# MacroMicro_v27.net
KiCad netlist of a schematic drawn in EAGLE
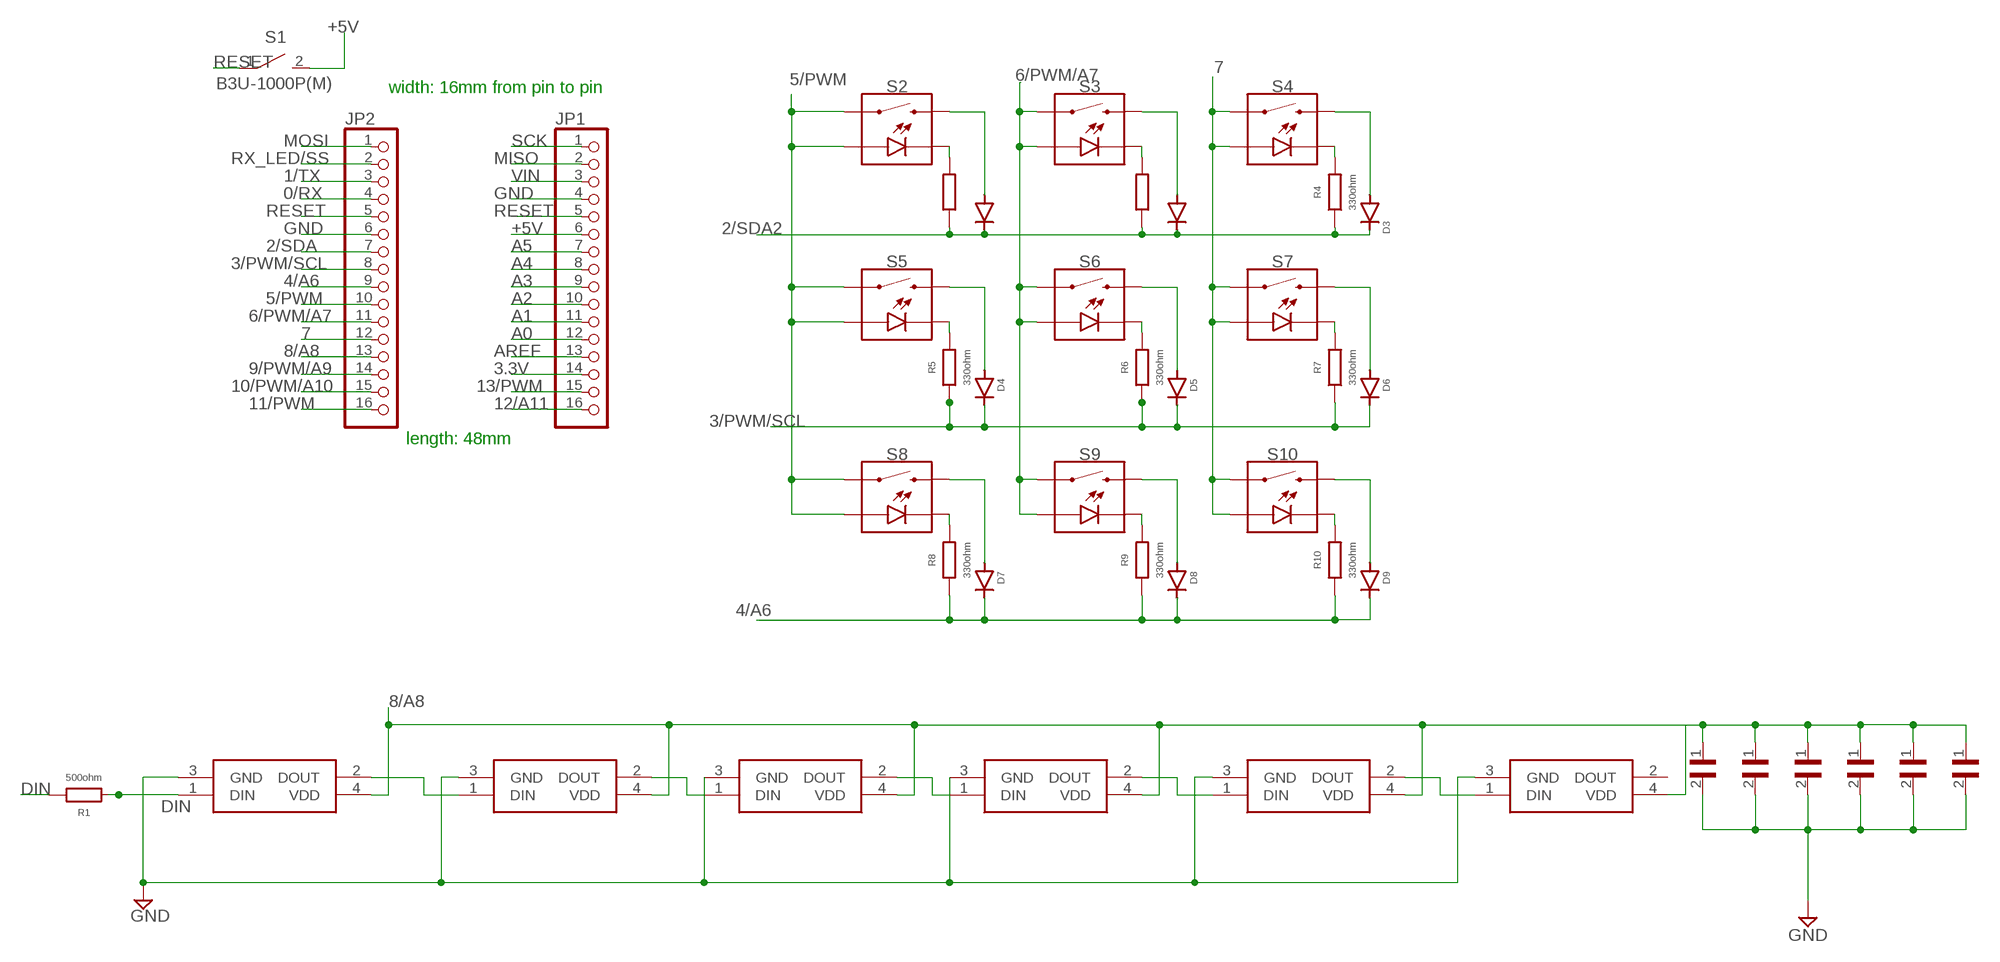
[diagram p0: schematic, sheet 1]

(export (version "E")
  (design (tool "Eeschema 10.0.6"))
  (components
    (comp (ref "C1")
      (value "0.1uf")
      (footprint "eagle-import:CAPC1608X80N")
      (fields
        (field (name "DIGI-KEY_PART_NUMBER") "1608-1306-1-ND")
        (field (name "MF") "Knowles Syfer")
        (field (name "MP") "0603Y0500104KET")
      )
      (libsource (lib "eagle-import") (part "0603Y0500104KET"))
    )
    (comp (ref "C2")
      (value "0.1uf")
      (footprint "eagle-import:CAPC1608X80N")
      (fields
        (field (name "DIGI-KEY_PART_NUMBER") "1608-1306-1-ND")
        (field (name "MF") "Knowles Syfer")
        (field (name "MP") "0603Y0500104KET")
      )
      (libsource (lib "eagle-import") (part "0603Y0500104KET"))
    )
    (comp (ref "C3")
      (value "0.1uf")
      (footprint "eagle-import:CAPC1608X80N")
      (fields
        (field (name "DIGI-KEY_PART_NUMBER") "1608-1306-1-ND")
        (field (name "MF") "Knowles Syfer")
        (field (name "MP") "0603Y0500104KET")
      )
      (libsource (lib "eagle-import") (part "0603Y0500104KET"))
    )
    (comp (ref "C4")
      (value "0.1uf")
      (footprint "eagle-import:CAPC1608X80N")
      (fields
        (field (name "DIGI-KEY_PART_NUMBER") "1608-1306-1-ND")
        (field (name "MF") "Knowles Syfer")
        (field (name "MP") "0603Y0500104KET")
      )
      (libsource (lib "eagle-import") (part "0603Y0500104KET"))
    )
    (comp (ref "C5")
      (value "0.1uf")
      (footprint "eagle-import:CAPC1608X80N")
      (fields
        (field (name "DIGI-KEY_PART_NUMBER") "1608-1306-1-ND")
        (field (name "MF") "Knowles Syfer")
        (field (name "MP") "0603Y0500104KET")
      )
      (libsource (lib "eagle-import") (part "0603Y0500104KET"))
    )
    (comp (ref "C6")
      (value "0.1uf")
      (footprint "eagle-import:CAPC1608X80N")
      (fields
        (field (name "DIGI-KEY_PART_NUMBER") "1608-1306-1-ND")
        (field (name "MF") "Knowles Syfer")
        (field (name "MP") "0603Y0500104KET")
      )
      (libsource (lib "eagle-import") (part "0603Y0500104KET"))
    )
    (comp (ref "D1")
      (value "1N4148WS")
      (footprint "eagle-import:SOD-323")
      (fields
        (field (name "DIGIKEY_PART_NUMBER") "1N4148WSFSTR-ND")
        (field (name "MANUFACTURER") "Diodes Incorporated")
        (field (name "CREATED_BY") "PCBLayout.com")
      )
      (libsource (lib "eagle-import") (part "1N4148WS"))
    )
    (comp (ref "D2")
      (value "1N4148WS")
      (footprint "eagle-import:SOD-323")
      (fields
        (field (name "DIGIKEY_PART_NUMBER") "1N4148WSFSTR-ND")
        (field (name "MANUFACTURER") "Diodes Incorporated")
        (field (name "CREATED_BY") "PCBLayout.com")
      )
      (libsource (lib "eagle-import") (part "1N4148WS"))
    )
    (comp (ref "D3")
      (value "1N4148WS")
      (footprint "eagle-import:SOD-323")
      (fields
        (field (name "DIGIKEY_PART_NUMBER") "1N4148WSFSTR-ND")
        (field (name "MANUFACTURER") "Diodes Incorporated")
        (field (name "CREATED_BY") "PCBLayout.com")
      )
      (libsource (lib "eagle-import") (part "1N4148WS"))
    )
    (comp (ref "D4")
      (value "1N4148WS")
      (footprint "eagle-import:SOD-323")
      (fields
        (field (name "DIGIKEY_PART_NUMBER") "1N4148WSFSTR-ND")
        (field (name "MANUFACTURER") "Diodes Incorporated")
        (field (name "CREATED_BY") "PCBLayout.com")
      )
      (libsource (lib "eagle-import") (part "1N4148WS"))
    )
    (comp (ref "D5")
      (value "1N4148WS")
      (footprint "eagle-import:SOD-323")
      (fields
        (field (name "DIGIKEY_PART_NUMBER") "1N4148WSFSTR-ND")
        (field (name "MANUFACTURER") "Diodes Incorporated")
        (field (name "CREATED_BY") "PCBLayout.com")
      )
      (libsource (lib "eagle-import") (part "1N4148WS"))
    )
    (comp (ref "D6")
      (value "1N4148WS")
      (footprint "eagle-import:SOD-323")
      (fields
        (field (name "DIGIKEY_PART_NUMBER") "1N4148WSFSTR-ND")
        (field (name "MANUFACTURER") "Diodes Incorporated")
        (field (name "CREATED_BY") "PCBLayout.com")
      )
      (libsource (lib "eagle-import") (part "1N4148WS"))
    )
    (comp (ref "D7")
      (value "1N4148WS")
      (footprint "eagle-import:SOD-323")
      (fields
        (field (name "DIGIKEY_PART_NUMBER") "1N4148WSFSTR-ND")
        (field (name "MANUFACTURER") "Diodes Incorporated")
        (field (name "CREATED_BY") "PCBLayout.com")
      )
      (libsource (lib "eagle-import") (part "1N4148WS"))
    )
    (comp (ref "D8")
      (value "1N4148WS")
      (footprint "eagle-import:SOD-323")
      (fields
        (field (name "DIGIKEY_PART_NUMBER") "1N4148WSFSTR-ND")
        (field (name "MANUFACTURER") "Diodes Incorporated")
        (field (name "CREATED_BY") "PCBLayout.com")
      )
      (libsource (lib "eagle-import") (part "1N4148WS"))
    )
    (comp (ref "D9")
      (value "1N4148WS")
      (footprint "eagle-import:SOD-323")
      (fields
        (field (name "DIGIKEY_PART_NUMBER") "1N4148WSFSTR-ND")
        (field (name "MANUFACTURER") "Diodes Incorporated")
        (field (name "CREATED_BY") "PCBLayout.com")
      )
      (libsource (lib "eagle-import") (part "1N4148WS"))
    )
    (comp (ref "JP1")
      (value "PINHD-1X16")
      (footprint "eagle-import:1X16")
      (libsource (lib "eagle-import") (part "PINHD-1X16"))
    )
    (comp (ref "JP2")
      (value "PINHD-1X16")
      (footprint "eagle-import:1X16")
      (libsource (lib "eagle-import") (part "PINHD-1X16"))
    )
    (comp (ref "LED1")
      (value "SK6812MINI-E")
      (footprint "eagle-import:SK6812MINIE")
      (libsource (lib "eagle-import") (part "SK6812MINI-E"))
    )
    (comp (ref "LED2")
      (value "SK6812MINI-E")
      (footprint "eagle-import:SK6812MINIE")
      (libsource (lib "eagle-import") (part "SK6812MINI-E"))
    )
    (comp (ref "LED3")
      (value "SK6812MINI-E")
      (footprint "eagle-import:SK6812MINIE")
      (libsource (lib "eagle-import") (part "SK6812MINI-E"))
    )
    (comp (ref "LED4")
      (value "SK6812MINI-E")
      (footprint "eagle-import:SK6812MINIE")
      (libsource (lib "eagle-import") (part "SK6812MINI-E"))
    )
    (comp (ref "LED5")
      (value "SK6812MINI-E")
      (footprint "eagle-import:SK6812MINIE")
      (libsource (lib "eagle-import") (part "SK6812MINI-E"))
    )
    (comp (ref "LED6")
      (value "SK6812MINI-E")
      (footprint "eagle-import:SK6812MINIE")
      (libsource (lib "eagle-import") (part "SK6812MINI-E"))
    )
    (comp (ref "R1")
      (value "500ohm")
      (footprint "eagle-import:RESC3216X70")
      (libsource (lib "eagle-import") (part "RCHIP-1206(3216-METRIC)_"))
    )
    (comp (ref "R2")
      (value "330ohm")
      (footprint "eagle-import:RESC3216X70")
      (libsource (lib "eagle-import") (part "RCHIP-1206(3216-METRIC)_"))
    )
    (comp (ref "R3")
      (value "330ohm")
      (footprint "eagle-import:RESC3216X70")
      (libsource (lib "eagle-import") (part "RCHIP-1206(3216-METRIC)_"))
    )
    (comp (ref "R4")
      (value "330ohm")
      (footprint "eagle-import:RESC3216X70")
      (libsource (lib "eagle-import") (part "RCHIP-1206(3216-METRIC)_"))
    )
    (comp (ref "R5")
      (value "330ohm")
      (footprint "eagle-import:RESC3216X70")
      (libsource (lib "eagle-import") (part "RCHIP-1206(3216-METRIC)_"))
    )
    (comp (ref "R6")
      (value "330ohm")
      (footprint "eagle-import:RESC3216X70")
      (libsource (lib "eagle-import") (part "RCHIP-1206(3216-METRIC)_"))
    )
    (comp (ref "R7")
      (value "330ohm")
      (footprint "eagle-import:RESC3216X70")
      (libsource (lib "eagle-import") (part "RCHIP-1206(3216-METRIC)_"))
    )
    (comp (ref "R8")
      (value "330ohm")
      (footprint "eagle-import:RESC3216X70")
      (libsource (lib "eagle-import") (part "RCHIP-1206(3216-METRIC)_"))
    )
    (comp (ref "R9")
      (value "330ohm")
      (footprint "eagle-import:RESC3216X70")
      (libsource (lib "eagle-import") (part "RCHIP-1206(3216-METRIC)_"))
    )
    (comp (ref "R10")
      (value "330ohm")
      (footprint "eagle-import:RESC3216X70")
      (libsource (lib "eagle-import") (part "RCHIP-1206(3216-METRIC)_"))
    )
    (comp (ref "S1")
      (value "B3U-1000P(M)")
      (footprint "eagle-import:B3U-1000P(M)")
      (fields (field (name "MANUFACTURER") "OMRON"))
      (libsource (lib "eagle-import") (part "B3U-X0001000P(M)B3U-1000P(M)"))
    )
    (comp (ref "S2")
      (value "MOMENTARY-SWITCH-SPST-LED-PTH-CHERRY")
      (footprint "eagle-import:CHERRY-MX-LED")
      (libsource (lib "eagle-import") (part "MOMENTARY-SWITCH-SPST-LED-PTH-CHERRY"))
    )
    (comp (ref "S3")
      (value "MOMENTARY-SWITCH-SPST-LED-PTH-CHERRY")
      (footprint "eagle-import:CHERRY-MX-LED")
      (libsource (lib "eagle-import") (part "MOMENTARY-SWITCH-SPST-LED-PTH-CHERRY"))
    )
    (comp (ref "S4")
      (value "MOMENTARY-SWITCH-SPST-LED-PTH-CHERRY")
      (footprint "eagle-import:CHERRY-MX-LED")
      (libsource (lib "eagle-import") (part "MOMENTARY-SWITCH-SPST-LED-PTH-CHERRY"))
    )
    (comp (ref "S5")
      (value "MOMENTARY-SWITCH-SPST-LED-PTH-CHERRY")
      (footprint "eagle-import:CHERRY-MX-LED")
      (libsource (lib "eagle-import") (part "MOMENTARY-SWITCH-SPST-LED-PTH-CHERRY"))
    )
    (comp (ref "S6")
      (value "MOMENTARY-SWITCH-SPST-LED-PTH-CHERRY")
      (footprint "eagle-import:CHERRY-MX-LED")
      (libsource (lib "eagle-import") (part "MOMENTARY-SWITCH-SPST-LED-PTH-CHERRY"))
    )
    (comp (ref "S7")
      (value "MOMENTARY-SWITCH-SPST-LED-PTH-CHERRY")
      (footprint "eagle-import:CHERRY-MX-LED")
      (libsource (lib "eagle-import") (part "MOMENTARY-SWITCH-SPST-LED-PTH-CHERRY"))
    )
    (comp (ref "S8")
      (value "MOMENTARY-SWITCH-SPST-LED-PTH-CHERRY")
      (footprint "eagle-import:CHERRY-MX-LED")
      (libsource (lib "eagle-import") (part "MOMENTARY-SWITCH-SPST-LED-PTH-CHERRY"))
    )
    (comp (ref "S9")
      (value "MOMENTARY-SWITCH-SPST-LED-PTH-CHERRY")
      (footprint "eagle-import:CHERRY-MX-LED")
      (libsource (lib "eagle-import") (part "MOMENTARY-SWITCH-SPST-LED-PTH-CHERRY"))
    )
    (comp (ref "S10")
      (value "MOMENTARY-SWITCH-SPST-LED-PTH-CHERRY")
      (footprint "eagle-import:CHERRY-MX-LED")
      (libsource (lib "eagle-import") (part "MOMENTARY-SWITCH-SPST-LED-PTH-CHERRY"))
    )
  )
  (nets
    (net (code "1") (name "/+5V") (class "Default")
      (node (ref "JP1") (pin "6") (pinfunction "6_6") (pintype "passive"))
      (node (ref "S1") (pin "2") (pinfunction "2_2") (pintype "bidirectional"))
    )
    (net (code "2") (name "/0{slash}RX") (class "Default")
      (node (ref "JP2") (pin "4") (pinfunction "4_4") (pintype "passive"))
    )
    (net (code "3") (name "/1{slash}TX") (class "Default")
      (node (ref "JP2") (pin "3") (pinfunction "3_3") (pintype "passive"))
    )
    (net (code "4") (name "/2{slash}SDA") (class "Default")
      (node (ref "JP2") (pin "7") (pinfunction "7_7") (pintype "passive"))
    )
    (net (code "5") (name "/2{slash}SDA2") (class "Default")
      (node (ref "D1") (pin "C") (pinfunction "C_C") (pintype "passive"))
      (node (ref "D2") (pin "C") (pinfunction "C_C") (pintype "passive"))
      (node (ref "D3") (pin "C") (pinfunction "C_C") (pintype "passive"))
      (node (ref "R2") (pin "1") (pinfunction "1_1") (pintype "passive"))
      (node (ref "R3") (pin "1") (pinfunction "1_1") (pintype "passive"))
      (node (ref "R4") (pin "1") (pinfunction "1_1") (pintype "passive"))
    )
    (net (code "6") (name "/3.3V") (class "Default")
      (node (ref "JP1") (pin "14") (pinfunction "14_14") (pintype "passive"))
    )
    (net (code "7") (name "/3{slash}PWM{slash}SCL") (class "Default")
      (node (ref "D4") (pin "C") (pinfunction "C_C") (pintype "passive"))
      (node (ref "D5") (pin "C") (pinfunction "C_C") (pintype "passive"))
      (node (ref "D6") (pin "C") (pinfunction "C_C") (pintype "passive"))
      (node (ref "JP2") (pin "8") (pinfunction "8_8") (pintype "passive"))
      (node (ref "R5") (pin "1") (pinfunction "1_1") (pintype "passive"))
      (node (ref "R6") (pin "1") (pinfunction "1_1") (pintype "passive"))
      (node (ref "R7") (pin "1") (pinfunction "1_1") (pintype "passive"))
    )
    (net (code "8") (name "/4{slash}A6") (class "Default")
      (node (ref "D7") (pin "C") (pinfunction "C_C") (pintype "passive"))
      (node (ref "D8") (pin "C") (pinfunction "C_C") (pintype "passive"))
      (node (ref "D9") (pin "C") (pinfunction "C_C") (pintype "passive"))
      (node (ref "JP2") (pin "9") (pinfunction "9_9") (pintype "passive"))
      (node (ref "R10") (pin "1") (pinfunction "1_1") (pintype "passive"))
      (node (ref "R8") (pin "1") (pinfunction "1_1") (pintype "passive"))
      (node (ref "R9") (pin "1") (pinfunction "1_1") (pintype "passive"))
    )
    (net (code "9") (name "/5{slash}PWM") (class "Default")
      (node (ref "JP2") (pin "10") (pinfunction "10_10") (pintype "passive"))
      (node (ref "S2") (pin "A") (pinfunction "A_A") (pintype "passive"))
      (node (ref "S2") (pin "S1") (pinfunction "1_S1") (pintype "passive"))
      (node (ref "S5") (pin "A") (pinfunction "A_A") (pintype "passive"))
      (node (ref "S5") (pin "S1") (pinfunction "1_S1") (pintype "passive"))
      (node (ref "S8") (pin "A") (pinfunction "A_A") (pintype "passive"))
      (node (ref "S8") (pin "S1") (pinfunction "1_S1") (pintype "passive"))
    )
    (net (code "10") (name "/6{slash}PWM{slash}A7") (class "Default")
      (node (ref "JP2") (pin "11") (pinfunction "11_11") (pintype "passive"))
      (node (ref "S3") (pin "A") (pinfunction "A_A") (pintype "passive"))
      (node (ref "S3") (pin "S1") (pinfunction "1_S1") (pintype "passive"))
      (node (ref "S6") (pin "A") (pinfunction "A_A") (pintype "passive"))
      (node (ref "S6") (pin "S1") (pinfunction "1_S1") (pintype "passive"))
      (node (ref "S9") (pin "A") (pinfunction "A_A") (pintype "passive"))
      (node (ref "S9") (pin "S1") (pinfunction "1_S1") (pintype "passive"))
    )
    (net (code "11") (name "/7") (class "Default")
      (node (ref "JP2") (pin "12") (pinfunction "12_12") (pintype "passive"))
      (node (ref "S10") (pin "A") (pinfunction "A_A") (pintype "passive"))
      (node (ref "S10") (pin "S1") (pinfunction "1_S1") (pintype "passive"))
      (node (ref "S4") (pin "A") (pinfunction "A_A") (pintype "passive"))
      (node (ref "S4") (pin "S1") (pinfunction "1_S1") (pintype "passive"))
      (node (ref "S7") (pin "A") (pinfunction "A_A") (pintype "passive"))
      (node (ref "S7") (pin "S1") (pinfunction "1_S1") (pintype "passive"))
    )
    (net (code "12") (name "/8{slash}A8") (class "Default")
      (node (ref "C1") (pin "1") (pinfunction "1_1") (pintype "passive"))
      (node (ref "C2") (pin "1") (pinfunction "1_1") (pintype "passive"))
      (node (ref "C3") (pin "1") (pinfunction "1_1") (pintype "passive"))
      (node (ref "C4") (pin "1") (pinfunction "1_1") (pintype "passive"))
      (node (ref "C5") (pin "1") (pinfunction "1_1") (pintype "passive"))
      (node (ref "C6") (pin "1") (pinfunction "1_1") (pintype "passive"))
      (node (ref "JP2") (pin "13") (pinfunction "13_13") (pintype "passive"))
      (node (ref "LED1") (pin "4") (pinfunction "VDD_4") (pintype "bidirectional"))
      (node (ref "LED2") (pin "4") (pinfunction "VDD_4") (pintype "bidirectional"))
      (node (ref "LED3") (pin "4") (pinfunction "VDD_4") (pintype "bidirectional"))
      (node (ref "LED4") (pin "4") (pinfunction "VDD_4") (pintype "bidirectional"))
      (node (ref "LED5") (pin "4") (pinfunction "VDD_4") (pintype "bidirectional"))
      (node (ref "LED6") (pin "4") (pinfunction "VDD_4") (pintype "bidirectional"))
    )
    (net (code "13") (name "/9{slash}PWM{slash}A9") (class "Default")
      (node (ref "JP2") (pin "14") (pinfunction "14_14") (pintype "passive"))
    )
    (net (code "14") (name "/10{slash}PWM{slash}A10") (class "Default")
      (node (ref "JP2") (pin "15") (pinfunction "15_15") (pintype "passive"))
    )
    (net (code "15") (name "/11{slash}PWM") (class "Default")
      (node (ref "JP2") (pin "16") (pinfunction "16_16") (pintype "passive"))
    )
    (net (code "16") (name "/12{slash}A11") (class "Default")
      (node (ref "JP1") (pin "16") (pinfunction "16_16") (pintype "passive"))
    )
    (net (code "17") (name "/13{slash}PWM") (class "Default")
      (node (ref "JP1") (pin "15") (pinfunction "15_15") (pintype "passive"))
    )
    (net (code "18") (name "/A0") (class "Default")
      (node (ref "JP1") (pin "12") (pinfunction "12_12") (pintype "passive"))
    )
    (net (code "19") (name "/A1") (class "Default")
      (node (ref "JP1") (pin "11") (pinfunction "11_11") (pintype "passive"))
    )
    (net (code "20") (name "/A2") (class "Default")
      (node (ref "JP1") (pin "10") (pinfunction "10_10") (pintype "passive"))
    )
    (net (code "21") (name "/A3") (class "Default")
      (node (ref "JP1") (pin "9") (pinfunction "9_9") (pintype "passive"))
    )
    (net (code "22") (name "/A4") (class "Default")
      (node (ref "JP1") (pin "8") (pinfunction "8_8") (pintype "passive"))
    )
    (net (code "23") (name "/A5") (class "Default")
      (node (ref "JP1") (pin "7") (pinfunction "7_7") (pintype "passive"))
    )
    (net (code "24") (name "/AREF") (class "Default")
      (node (ref "JP1") (pin "13") (pinfunction "13_13") (pintype "passive"))
    )
    (net (code "25") (name "/DIN") (class "Default")
      (node (ref "LED1") (pin "1") (pinfunction "DIN_1") (pintype "bidirectional"))
      (node (ref "R1") (pin "1") (pinfunction "1_1") (pintype "passive"))
      (node (ref "R1") (pin "2") (pinfunction "2_2") (pintype "passive"))
    )
    (net (code "26") (name "/MISO") (class "Default")
      (node (ref "JP1") (pin "2") (pinfunction "2_2") (pintype "passive"))
    )
    (net (code "27") (name "/MOSI") (class "Default")
      (node (ref "JP2") (pin "1") (pinfunction "1_1") (pintype "passive"))
    )
    (net (code "28") (name "/RESET") (class "Default")
      (node (ref "JP1") (pin "5") (pinfunction "5_5") (pintype "passive"))
      (node (ref "JP2") (pin "5") (pinfunction "5_5") (pintype "passive"))
      (node (ref "S1") (pin "1") (pinfunction "1_1") (pintype "bidirectional"))
    )
    (net (code "29") (name "/RX_LED{slash}SS") (class "Default")
      (node (ref "JP2") (pin "2") (pinfunction "2_2") (pintype "passive"))
    )
    (net (code "30") (name "/SCK") (class "Default")
      (node (ref "JP1") (pin "1") (pinfunction "1_1") (pintype "passive"))
    )
    (net (code "31") (name "/VIN") (class "Default")
      (node (ref "JP1") (pin "3") (pinfunction "3_3") (pintype "passive"))
    )
    (net (code "32") (name "GND") (class "Default")
      (node (ref "C1") (pin "2") (pinfunction "2_2") (pintype "passive"))
      (node (ref "C2") (pin "2") (pinfunction "2_2") (pintype "passive"))
      (node (ref "C3") (pin "2") (pinfunction "2_2") (pintype "passive"))
      (node (ref "C4") (pin "2") (pinfunction "2_2") (pintype "passive"))
      (node (ref "C5") (pin "2") (pinfunction "2_2") (pintype "passive"))
      (node (ref "C6") (pin "2") (pinfunction "2_2") (pintype "passive"))
      (node (ref "JP1") (pin "4") (pinfunction "4_4") (pintype "passive"))
      (node (ref "JP2") (pin "6") (pinfunction "6_6") (pintype "passive"))
      (node (ref "LED1") (pin "3") (pinfunction "GND_3") (pintype "bidirectional"))
      (node (ref "LED2") (pin "3") (pinfunction "GND_3") (pintype "bidirectional"))
      (node (ref "LED3") (pin "3") (pinfunction "GND_3") (pintype "bidirectional"))
      (node (ref "LED4") (pin "3") (pinfunction "GND_3") (pintype "bidirectional"))
      (node (ref "LED5") (pin "3") (pinfunction "GND_3") (pintype "bidirectional"))
      (node (ref "LED6") (pin "3") (pinfunction "GND_3") (pintype "bidirectional"))
    )
    (net (code "33") (name "Net-(LED1-DOUT)") (class "Default")
      (node (ref "LED1") (pin "2") (pinfunction "DOUT_2") (pintype "bidirectional"))
      (node (ref "LED2") (pin "1") (pinfunction "DIN_1") (pintype "bidirectional"))
    )
    (net (code "34") (name "Net-(LED2-DOUT)") (class "Default")
      (node (ref "LED2") (pin "2") (pinfunction "DOUT_2") (pintype "bidirectional"))
      (node (ref "LED3") (pin "1") (pinfunction "DIN_1") (pintype "bidirectional"))
    )
    (net (code "35") (name "Net-(LED3-DOUT)") (class "Default")
      (node (ref "LED3") (pin "2") (pinfunction "DOUT_2") (pintype "bidirectional"))
      (node (ref "LED4") (pin "1") (pinfunction "DIN_1") (pintype "bidirectional"))
    )
    (net (code "36") (name "Net-(LED4-DOUT)") (class "Default")
      (node (ref "LED4") (pin "2") (pinfunction "DOUT_2") (pintype "bidirectional"))
      (node (ref "LED5") (pin "1") (pinfunction "DIN_1") (pintype "bidirectional"))
    )
    (net (code "37") (name "Net-(LED5-DOUT)") (class "Default")
      (node (ref "LED5") (pin "2") (pinfunction "DOUT_2") (pintype "bidirectional"))
      (node (ref "LED6") (pin "1") (pinfunction "DIN_1") (pintype "bidirectional"))
    )
    (net (code "38") (name "Net-(S2-2)") (class "Default")
      (node (ref "D1") (pin "A") (pinfunction "A_A") (pintype "passive"))
      (node (ref "S2") (pin "S2") (pinfunction "2_S2") (pintype "passive"))
    )
    (net (code "39") (name "Net-(S2-C)") (class "Default")
      (node (ref "R2") (pin "2") (pinfunction "2_2") (pintype "passive"))
      (node (ref "S2") (pin "K") (pinfunction "C_K") (pintype "passive"))
    )
    (net (code "40") (name "Net-(S3-2)") (class "Default")
      (node (ref "D2") (pin "A") (pinfunction "A_A") (pintype "passive"))
      (node (ref "S3") (pin "S2") (pinfunction "2_S2") (pintype "passive"))
    )
    (net (code "41") (name "Net-(S3-C)") (class "Default")
      (node (ref "R3") (pin "2") (pinfunction "2_2") (pintype "passive"))
      (node (ref "S3") (pin "K") (pinfunction "C_K") (pintype "passive"))
    )
    (net (code "42") (name "Net-(S4-2)") (class "Default")
      (node (ref "D3") (pin "A") (pinfunction "A_A") (pintype "passive"))
      (node (ref "S4") (pin "S2") (pinfunction "2_S2") (pintype "passive"))
    )
    (net (code "43") (name "Net-(S4-C)") (class "Default")
      (node (ref "R4") (pin "2") (pinfunction "2_2") (pintype "passive"))
      (node (ref "S4") (pin "K") (pinfunction "C_K") (pintype "passive"))
    )
    (net (code "44") (name "Net-(S5-2)") (class "Default")
      (node (ref "D4") (pin "A") (pinfunction "A_A") (pintype "passive"))
      (node (ref "S5") (pin "S2") (pinfunction "2_S2") (pintype "passive"))
    )
    (net (code "45") (name "Net-(S5-C)") (class "Default")
      (node (ref "R5") (pin "2") (pinfunction "2_2") (pintype "passive"))
      (node (ref "S5") (pin "K") (pinfunction "C_K") (pintype "passive"))
    )
    (net (code "46") (name "Net-(S6-2)") (class "Default")
      (node (ref "D5") (pin "A") (pinfunction "A_A") (pintype "passive"))
      (node (ref "S6") (pin "S2") (pinfunction "2_S2") (pintype "passive"))
    )
    (net (code "47") (name "Net-(S6-C)") (class "Default")
      (node (ref "R6") (pin "2") (pinfunction "2_2") (pintype "passive"))
      (node (ref "S6") (pin "K") (pinfunction "C_K") (pintype "passive"))
    )
    (net (code "48") (name "Net-(S7-2)") (class "Default")
      (node (ref "D6") (pin "A") (pinfunction "A_A") (pintype "passive"))
      (node (ref "S7") (pin "S2") (pinfunction "2_S2") (pintype "passive"))
    )
    (net (code "49") (name "Net-(S7-C)") (class "Default")
      (node (ref "R7") (pin "2") (pinfunction "2_2") (pintype "passive"))
      (node (ref "S7") (pin "K") (pinfunction "C_K") (pintype "passive"))
    )
    (net (code "50") (name "Net-(S8-2)") (class "Default")
      (node (ref "D7") (pin "A") (pinfunction "A_A") (pintype "passive"))
      (node (ref "S8") (pin "S2") (pinfunction "2_S2") (pintype "passive"))
    )
    (net (code "51") (name "Net-(S8-C)") (class "Default")
      (node (ref "R8") (pin "2") (pinfunction "2_2") (pintype "passive"))
      (node (ref "S8") (pin "K") (pinfunction "C_K") (pintype "passive"))
    )
    (net (code "52") (name "Net-(S9-2)") (class "Default")
      (node (ref "D8") (pin "A") (pinfunction "A_A") (pintype "passive"))
      (node (ref "S9") (pin "S2") (pinfunction "2_S2") (pintype "passive"))
    )
    (net (code "53") (name "Net-(S9-C)") (class "Default")
      (node (ref "R9") (pin "2") (pinfunction "2_2") (pintype "passive"))
      (node (ref "S9") (pin "K") (pinfunction "C_K") (pintype "passive"))
    )
    (net (code "54") (name "Net-(S10-2)") (class "Default")
      (node (ref "D9") (pin "A") (pinfunction "A_A") (pintype "passive"))
      (node (ref "S10") (pin "S2") (pinfunction "2_S2") (pintype "passive"))
    )
    (net (code "55") (name "Net-(S10-C)") (class "Default")
      (node (ref "R10") (pin "2") (pinfunction "2_2") (pintype "passive"))
      (node (ref "S10") (pin "K") (pinfunction "C_K") (pintype "passive"))
    )
    (net (code "56") (name "unconnected-(LED6-DOUT-Pad2)") (class "Default")
      (node (ref "LED6") (pin "2") (pinfunction "DOUT_2") (pintype "bidirectional"))
    )
  )
)
